# Battery_Management.net
KiCad netlist of a schematic drawn in Altium Designer
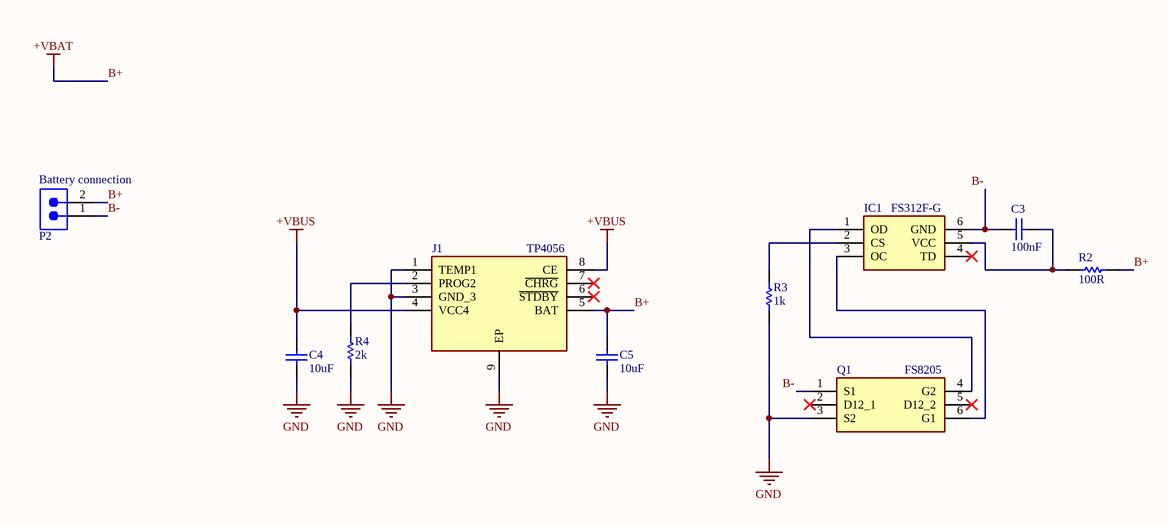
[diagram p0: Battery_Management.SchDoc]

(export (version "E")
  (design (tool "Eeschema 10.0.6"))
  (components
    (comp (ref "C3")
      (value "100nF")
      (footprint "Wurth 0603 capacitor")
      (fields (field (name "Comment") "Generic Capacitor 100nF 0603"))
      (libsource (lib "Passives") (part "Generic Capacitor 100nF 0603"))
    )
    (comp (ref "C4")
      (value "10uF")
      (footprint "Wurth 0603 capacitor")
      (fields (field (name "Comment") "Generic Capacitor 10uF 0603"))
      (libsource (lib "Passives") (part "Generic Capacitor 10uF 0603"))
    )
    (comp (ref "C5")
      (value "10uF")
      (footprint "Wurth 0603 capacitor")
      (fields (field (name "Comment") "Generic Capacitor 10uF 0603"))
      (libsource (lib "Passives") (part "Generic Capacitor 10uF 0603"))
    )
    (comp (ref "IC1")
      (value "FS312F-G")
      (footprint "SamacSys:SOT95P280X145-6N")
      (description "Integrated Circuit")
      (libsource (lib "*") (part "FS312F-G"))
    )
    (comp (ref "J1")
      (value "TP4056")
      (footprint "SamacSys:SOIC127P600X175-9N")
      (description "Connector")
      (libsource (lib "*") (part "TP4056"))
    )
    (comp (ref "P2")
      (value "Battery connection")
      (footprint "2x1 2.54mm")
      (description "WR-PHD Pin Header, THT, Vertical, pitch 2.54mm, 1 Row, 2P")
      (fields
        (field (name "MANUFACTURER PART NUMBER") "61300211121")
        (field (name "MANUFACTURER") "Wurth Elektronik")
      )
      (libsource (lib "2.54mm_pin_headers") (part "61300211121"))
    )
    (comp (ref "Q1")
      (value "FS8205")
      (footprint "SamacSys:FS8205")
      (description "MOSFET (N-Channel)")
      (libsource (lib "*") (part "FS8205"))
    )
    (comp (ref "R2")
      (value "100R")
      (footprint "Wurth 0603 Resistor")
      (fields (field (name "Comment") "Generic Resistor 100R 0603"))
      (libsource (lib "Passives") (part "Generic Resistor 100R 0603"))
    )
    (comp (ref "R3")
      (value "1k")
      (footprint "Wurth 0603 Resistor")
      (fields (field (name "Comment") "Generic Resistor 1k 0603"))
      (libsource (lib "Passives") (part "Generic Resistor 1k 0603"))
    )
    (comp (ref "R4")
      (value "2k")
      (footprint "Wurth 0603 Resistor")
      (fields (field (name "Comment") "Generic Resistor 2k 0603"))
      (libsource (lib "Passives") (part "Generic Resistor 2k 0603"))
    )
  )
  (nets
    (net (code "1") (name "+VBAT") (class "Default")
      (node (ref "C5") (pin "2") (pinfunction "2_2") (pintype "passive"))
      (node (ref "J1") (pin "5") (pinfunction "BAT_5") (pintype "passive"))
      (node (ref "P2") (pin "2") (pinfunction "2_2") (pintype "passive"))
      (node (ref "R2") (pin "2") (pinfunction "2_2") (pintype "passive"))
    )
    (net (code "2") (name "+VBUS") (class "Default")
      (node (ref "C4") (pin "2") (pinfunction "2_2") (pintype "passive"))
      (node (ref "J1") (pin "4") (pinfunction "VCC4_4") (pintype "passive"))
      (node (ref "J1") (pin "8") (pinfunction "CE_8") (pintype "passive"))
    )
    (net (code "3") (name "/B-") (class "Default")
      (node (ref "C3") (pin "1") (pinfunction "1_1") (pintype "passive"))
      (node (ref "IC1") (pin "6") (pinfunction "GND_6") (pintype "passive"))
      (node (ref "P2") (pin "1") (pinfunction "1_1") (pintype "passive"))
      (node (ref "Q1") (pin "1") (pinfunction "S1_1") (pintype "passive"))
    )
    (net (code "4") (name "GND") (class "Default")
      (node (ref "C4") (pin "1") (pinfunction "1_1") (pintype "passive"))
      (node (ref "C5") (pin "1") (pinfunction "1_1") (pintype "passive"))
      (node (ref "J1") (pin "1") (pinfunction "TEMP1_1") (pintype "passive"))
      (node (ref "J1") (pin "3") (pinfunction "GND_3_3") (pintype "passive"))
      (node (ref "J1") (pin "9") (pinfunction "EP_9") (pintype "passive"))
      (node (ref "Q1") (pin "3") (pinfunction "S2_3") (pintype "passive"))
      (node (ref "R3") (pin "1") (pinfunction "1_1") (pintype "passive"))
      (node (ref "R4") (pin "1") (pinfunction "1_1") (pintype "passive"))
    )
    (net (code "5") (name "Net-(IC1-CS)") (class "Default")
      (node (ref "IC1") (pin "2") (pinfunction "CS_2") (pintype "passive"))
      (node (ref "R3") (pin "2") (pinfunction "2_2") (pintype "passive"))
    )
    (net (code "6") (name "Net-(IC1-OC)") (class "Default")
      (node (ref "IC1") (pin "3") (pinfunction "OC_3") (pintype "passive"))
      (node (ref "Q1") (pin "6") (pinfunction "G1_6") (pintype "passive"))
    )
    (net (code "7") (name "Net-(IC1-OD)") (class "Default")
      (node (ref "IC1") (pin "1") (pinfunction "OD_1") (pintype "passive"))
      (node (ref "Q1") (pin "4") (pinfunction "G2_4") (pintype "passive"))
    )
    (net (code "8") (name "Net-(IC1-VCC)") (class "Default")
      (node (ref "C3") (pin "2") (pinfunction "2_2") (pintype "passive"))
      (node (ref "IC1") (pin "5") (pinfunction "VCC_5") (pintype "passive"))
      (node (ref "R2") (pin "1") (pinfunction "1_1") (pintype "passive"))
    )
    (net (code "9") (name "Net-(J1-PROG2)") (class "Default")
      (node (ref "J1") (pin "2") (pinfunction "PROG2_2") (pintype "passive"))
      (node (ref "R4") (pin "2") (pinfunction "2_2") (pintype "passive"))
    )
    (net (code "10") (name "unconnected-(IC1-TD-Pad4)") (class "Default")
      (node (ref "IC1") (pin "4") (pinfunction "TD_4") (pintype "passive+no_connect"))
    )
    (net (code "11") (name "unconnected-(J1-~{CHRG}-Pad7)") (class "Default")
      (node (ref "J1") (pin "7") (pinfunction "~{CHRG}_7") (pintype "passive+no_connect"))
    )
    (net (code "12") (name "unconnected-(J1-~{STDBY}-Pad6)") (class "Default")
      (node (ref "J1") (pin "6") (pinfunction "~{STDBY}_6") (pintype "passive+no_connect"))
    )
    (net (code "13") (name "unconnected-(Q1-D12_1-Pad2)") (class "Default")
      (node (ref "Q1") (pin "2") (pinfunction "D12_1_2") (pintype "passive+no_connect"))
    )
    (net (code "14") (name "unconnected-(Q1-D12_2-Pad5)") (class "Default")
      (node (ref "Q1") (pin "5") (pinfunction "D12_2_5") (pintype "passive+no_connect"))
    )
  )
)
